# diy_drivermotor.net
KiCad netlist of a schematic drawn in EAGLE
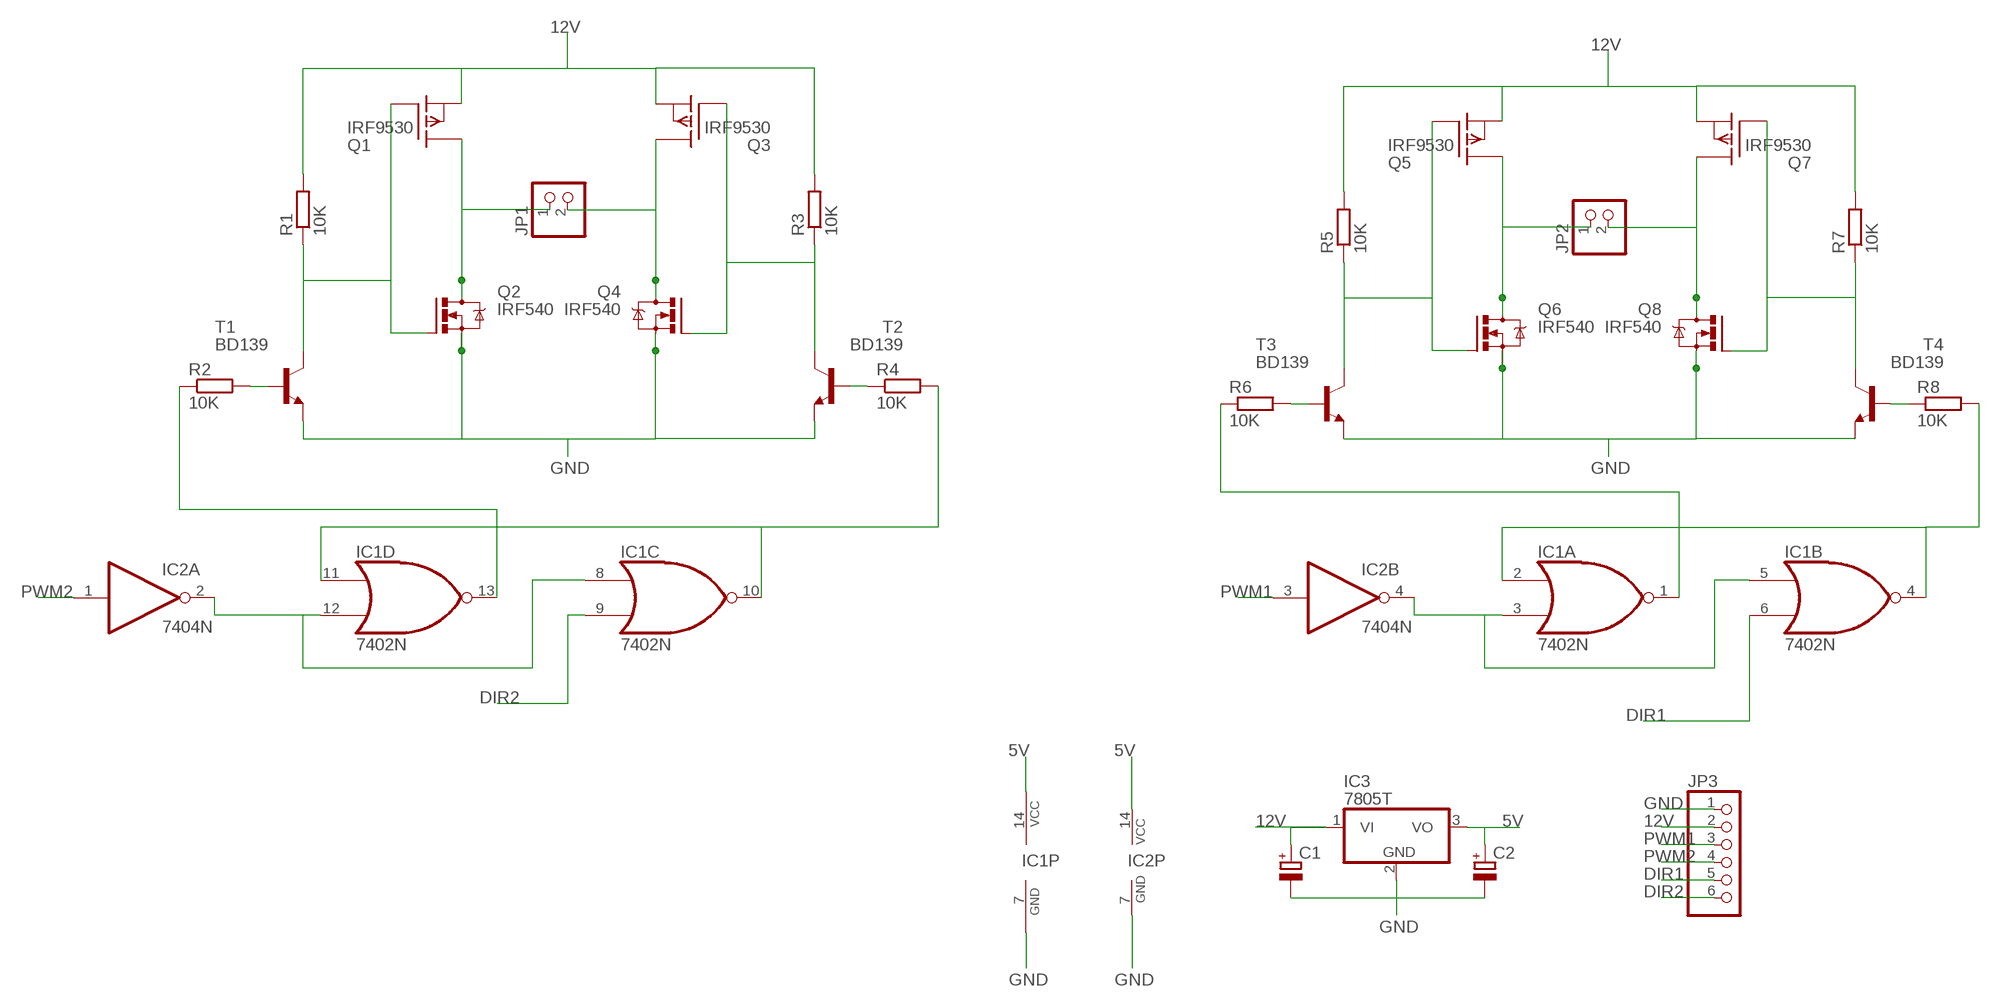
[diagram p0: schematic, sheet 1]

(export (version "E")
  (design (tool "Eeschema 10.0.6"))
  (components
    (comp (ref "C1")
      (value "CPOL-EUE2.5-6")
      (footprint "eagle-import:E2,5-6")
      (libsource (lib "eagle-import") (part "CPOL-EUE2.5-6"))
    )
    (comp (ref "C2")
      (value "CPOL-EUE2.5-6")
      (footprint "eagle-import:E2,5-6")
      (libsource (lib "eagle-import") (part "CPOL-EUE2.5-6"))
    )
    (comp (ref "IC1")
      (value "7402N")
      (footprint "eagle-import:DIL14")
      (libsource (lib "eagle-import") (part "7402N"))
    )
    (comp (ref "IC2")
      (value "7404N")
      (footprint "eagle-import:DIL14")
      (libsource (lib "eagle-import") (part "7404N"))
    )
    (comp (ref "IC3")
      (value "7805T")
      (footprint "eagle-import:TO220H")
      (libsource (lib "eagle-import") (part "78T05"))
    )
    (comp (ref "JP1")
      (value "PINHD-1X2")
      (footprint "eagle-import:1X02")
      (libsource (lib "eagle-import") (part "PINHD-1X2"))
    )
    (comp (ref "JP2")
      (value "PINHD-1X2")
      (footprint "eagle-import:1X02")
      (libsource (lib "eagle-import") (part "PINHD-1X2"))
    )
    (comp (ref "JP3")
      (value "PINHD-1X6")
      (footprint "eagle-import:1X06")
      (libsource (lib "eagle-import") (part "PINHD-1X6"))
    )
    (comp (ref "Q1")
      (value "IRF9530")
      (footprint "eagle-import:TO220")
      (libsource (lib "eagle-import") (part "IRF9530"))
    )
    (comp (ref "Q2")
      (value "IRF540")
      (footprint "eagle-import:TO220BV")
      (libsource (lib "eagle-import") (part "IRF540"))
    )
    (comp (ref "Q3")
      (value "IRF9530")
      (footprint "eagle-import:TO220")
      (libsource (lib "eagle-import") (part "IRF9530"))
    )
    (comp (ref "Q4")
      (value "IRF540")
      (footprint "eagle-import:TO220BV")
      (libsource (lib "eagle-import") (part "IRF540"))
    )
    (comp (ref "Q5")
      (value "IRF9530")
      (footprint "eagle-import:TO220")
      (libsource (lib "eagle-import") (part "IRF9530"))
    )
    (comp (ref "Q6")
      (value "IRF540")
      (footprint "eagle-import:TO220BV")
      (libsource (lib "eagle-import") (part "IRF540"))
    )
    (comp (ref "Q7")
      (value "IRF9530")
      (footprint "eagle-import:TO220")
      (libsource (lib "eagle-import") (part "IRF9530"))
    )
    (comp (ref "Q8")
      (value "IRF540")
      (footprint "eagle-import:TO220BV")
      (libsource (lib "eagle-import") (part "IRF540"))
    )
    (comp (ref "R1")
      (value "10K")
      (footprint "eagle-import:0207_7")
      (libsource (lib "eagle-import") (part "R-EU_0207/7"))
    )
    (comp (ref "R2")
      (value "10K")
      (footprint "eagle-import:0207_7")
      (libsource (lib "eagle-import") (part "R-EU_0207/7"))
    )
    (comp (ref "R3")
      (value "10K")
      (footprint "eagle-import:0207_7")
      (libsource (lib "eagle-import") (part "R-EU_0207/7"))
    )
    (comp (ref "R4")
      (value "10K")
      (footprint "eagle-import:0207_7")
      (libsource (lib "eagle-import") (part "R-EU_0207/7"))
    )
    (comp (ref "R5")
      (value "10K")
      (footprint "eagle-import:0207_7")
      (libsource (lib "eagle-import") (part "R-EU_0207/7"))
    )
    (comp (ref "R6")
      (value "10K")
      (footprint "eagle-import:0207_7")
      (libsource (lib "eagle-import") (part "R-EU_0207/7"))
    )
    (comp (ref "R7")
      (value "10K")
      (footprint "eagle-import:0207_7")
      (libsource (lib "eagle-import") (part "R-EU_0207/7"))
    )
    (comp (ref "R8")
      (value "10K")
      (footprint "eagle-import:0207_7")
      (libsource (lib "eagle-import") (part "R-EU_0207/7"))
    )
    (comp (ref "T1")
      (value "BD139")
      (footprint "eagle-import:TO126")
      (libsource (lib "eagle-import") (part "BD139"))
    )
    (comp (ref "T2")
      (value "BD139")
      (footprint "eagle-import:TO126")
      (libsource (lib "eagle-import") (part "BD139"))
    )
    (comp (ref "T3")
      (value "BD139")
      (footprint "eagle-import:TO126")
      (libsource (lib "eagle-import") (part "BD139"))
    )
    (comp (ref "T4")
      (value "BD139")
      (footprint "eagle-import:TO126")
      (libsource (lib "eagle-import") (part "BD139"))
    )
  )
  (nets
    (net (code "1") (name "/5V") (class "Default")
      (node (ref "C2") (pin "+") (pinfunction "+_+") (pintype "passive"))
      (node (ref "IC1") (pin "14") (pinfunction "VCC_14") (pintype "power_in"))
      (node (ref "IC2") (pin "14") (pinfunction "VCC_14") (pintype "power_in"))
      (node (ref "IC3") (pin "3") (pinfunction "VO_3") (pintype "passive"))
    )
    (net (code "2") (name "/12V") (class "Default")
      (node (ref "C1") (pin "+") (pinfunction "+_+") (pintype "passive"))
      (node (ref "IC3") (pin "1") (pinfunction "VI_1") (pintype "input"))
      (node (ref "JP3") (pin "2") (pinfunction "2_2") (pintype "passive"))
      (node (ref "Q1") (pin "3") (pinfunction "S_3") (pintype "passive"))
      (node (ref "Q3") (pin "3") (pinfunction "S_3") (pintype "passive"))
      (node (ref "Q5") (pin "3") (pinfunction "S_3") (pintype "passive"))
      (node (ref "Q7") (pin "3") (pinfunction "S_3") (pintype "passive"))
      (node (ref "R1") (pin "2") (pinfunction "2_2") (pintype "passive"))
      (node (ref "R3") (pin "2") (pinfunction "2_2") (pintype "passive"))
      (node (ref "R5") (pin "2") (pinfunction "2_2") (pintype "passive"))
      (node (ref "R7") (pin "2") (pinfunction "2_2") (pintype "passive"))
    )
    (net (code "3") (name "/DIR1") (class "Default")
      (node (ref "IC1") (pin "6") (pinfunction "I1_6") (pintype "input"))
      (node (ref "JP3") (pin "5") (pinfunction "5_5") (pintype "passive"))
    )
    (net (code "4") (name "/DIR2") (class "Default")
      (node (ref "IC1") (pin "9") (pinfunction "I1_9") (pintype "input"))
      (node (ref "JP3") (pin "6") (pinfunction "6_6") (pintype "passive"))
    )
    (net (code "5") (name "/GND") (class "Default")
      (node (ref "C1") (pin "-") (pinfunction "-_-") (pintype "passive"))
      (node (ref "C2") (pin "-") (pinfunction "-_-") (pintype "passive"))
      (node (ref "IC1") (pin "7") (pinfunction "GND_7") (pintype "power_in"))
      (node (ref "IC2") (pin "7") (pinfunction "GND_7") (pintype "power_in"))
      (node (ref "IC3") (pin "2") (pinfunction "GND_2") (pintype "passive"))
      (node (ref "JP3") (pin "1") (pinfunction "1_1") (pintype "passive"))
      (node (ref "Q2") (pin "S") (pinfunction "S_S") (pintype "passive"))
      (node (ref "Q4") (pin "S") (pinfunction "S_S") (pintype "passive"))
      (node (ref "Q6") (pin "S") (pinfunction "S_S") (pintype "passive"))
      (node (ref "Q8") (pin "S") (pinfunction "S_S") (pintype "passive"))
      (node (ref "T1") (pin "1") (pinfunction "E_1") (pintype "passive"))
      (node (ref "T2") (pin "1") (pinfunction "E_1") (pintype "passive"))
      (node (ref "T3") (pin "1") (pinfunction "E_1") (pintype "passive"))
      (node (ref "T4") (pin "1") (pinfunction "E_1") (pintype "passive"))
    )
    (net (code "6") (name "/PWM1") (class "Default")
      (node (ref "IC2") (pin "3") (pinfunction "I_3") (pintype "input"))
      (node (ref "JP3") (pin "3") (pinfunction "3_3") (pintype "passive"))
    )
    (net (code "7") (name "/PWM2") (class "Default")
      (node (ref "IC2") (pin "1") (pinfunction "I_1") (pintype "input"))
      (node (ref "JP3") (pin "4") (pinfunction "4_4") (pintype "passive"))
    )
    (net (code "8") (name "Net-(IC1A-I0)") (class "Default")
      (node (ref "IC1") (pin "2") (pinfunction "I0_2") (pintype "input"))
      (node (ref "IC1") (pin "4") (pinfunction "O_4") (pintype "output"))
      (node (ref "R8") (pin "2") (pinfunction "2_2") (pintype "passive"))
    )
    (net (code "9") (name "Net-(IC1A-I1)") (class "Default")
      (node (ref "IC1") (pin "3") (pinfunction "I1_3") (pintype "input"))
      (node (ref "IC1") (pin "5") (pinfunction "I0_5") (pintype "input"))
      (node (ref "IC2") (pin "4") (pinfunction "O_4") (pintype "output"))
    )
    (net (code "10") (name "Net-(IC1A-O)") (class "Default")
      (node (ref "IC1") (pin "1") (pinfunction "O_1") (pintype "output"))
      (node (ref "R6") (pin "1") (pinfunction "1_1") (pintype "passive"))
    )
    (net (code "11") (name "Net-(IC1C-I0)") (class "Default")
      (node (ref "IC1") (pin "12") (pinfunction "I1_12") (pintype "input"))
      (node (ref "IC1") (pin "8") (pinfunction "I0_8") (pintype "input"))
      (node (ref "IC2") (pin "2") (pinfunction "O_2") (pintype "output"))
    )
    (net (code "12") (name "Net-(IC1C-O)") (class "Default")
      (node (ref "IC1") (pin "10") (pinfunction "O_10") (pintype "output"))
      (node (ref "IC1") (pin "11") (pinfunction "I0_11") (pintype "input"))
      (node (ref "R4") (pin "2") (pinfunction "2_2") (pintype "passive"))
    )
    (net (code "13") (name "Net-(IC1D-O)") (class "Default")
      (node (ref "IC1") (pin "13") (pinfunction "O_13") (pintype "output"))
      (node (ref "R2") (pin "1") (pinfunction "1_1") (pintype "passive"))
    )
    (net (code "14") (name "Net-(Q1-D)") (class "Default")
      (node (ref "JP1") (pin "1") (pinfunction "1_1") (pintype "passive"))
      (node (ref "Q1") (pin "2") (pinfunction "D_2") (pintype "passive"))
      (node (ref "Q2") (pin "D") (pinfunction "D_D") (pintype "passive"))
    )
    (net (code "15") (name "Net-(Q1-G)") (class "Default")
      (node (ref "Q1") (pin "1") (pinfunction "G_1") (pintype "passive"))
      (node (ref "Q2") (pin "G") (pinfunction "G_G") (pintype "passive"))
      (node (ref "R1") (pin "1") (pinfunction "1_1") (pintype "passive"))
      (node (ref "T1") (pin "2") (pinfunction "C_2") (pintype "passive"))
    )
    (net (code "16") (name "Net-(Q3-D)") (class "Default")
      (node (ref "JP1") (pin "2") (pinfunction "2_2") (pintype "passive"))
      (node (ref "Q3") (pin "2") (pinfunction "D_2") (pintype "passive"))
      (node (ref "Q4") (pin "D") (pinfunction "D_D") (pintype "passive"))
    )
    (net (code "17") (name "Net-(Q3-G)") (class "Default")
      (node (ref "Q3") (pin "1") (pinfunction "G_1") (pintype "passive"))
      (node (ref "Q4") (pin "G") (pinfunction "G_G") (pintype "passive"))
      (node (ref "R3") (pin "1") (pinfunction "1_1") (pintype "passive"))
      (node (ref "T2") (pin "2") (pinfunction "C_2") (pintype "passive"))
    )
    (net (code "18") (name "Net-(Q5-D)") (class "Default")
      (node (ref "JP2") (pin "1") (pinfunction "1_1") (pintype "passive"))
      (node (ref "Q5") (pin "2") (pinfunction "D_2") (pintype "passive"))
      (node (ref "Q6") (pin "D") (pinfunction "D_D") (pintype "passive"))
    )
    (net (code "19") (name "Net-(Q5-G)") (class "Default")
      (node (ref "Q5") (pin "1") (pinfunction "G_1") (pintype "passive"))
      (node (ref "Q6") (pin "G") (pinfunction "G_G") (pintype "passive"))
      (node (ref "R5") (pin "1") (pinfunction "1_1") (pintype "passive"))
      (node (ref "T3") (pin "2") (pinfunction "C_2") (pintype "passive"))
    )
    (net (code "20") (name "Net-(Q7-D)") (class "Default")
      (node (ref "JP2") (pin "2") (pinfunction "2_2") (pintype "passive"))
      (node (ref "Q7") (pin "2") (pinfunction "D_2") (pintype "passive"))
      (node (ref "Q8") (pin "D") (pinfunction "D_D") (pintype "passive"))
    )
    (net (code "21") (name "Net-(Q7-G)") (class "Default")
      (node (ref "Q7") (pin "1") (pinfunction "G_1") (pintype "passive"))
      (node (ref "Q8") (pin "G") (pinfunction "G_G") (pintype "passive"))
      (node (ref "R7") (pin "1") (pinfunction "1_1") (pintype "passive"))
      (node (ref "T4") (pin "2") (pinfunction "C_2") (pintype "passive"))
    )
    (net (code "22") (name "Net-(T1-B)") (class "Default")
      (node (ref "R2") (pin "2") (pinfunction "2_2") (pintype "passive"))
      (node (ref "T1") (pin "3") (pinfunction "B_3") (pintype "passive"))
    )
    (net (code "23") (name "Net-(T2-B)") (class "Default")
      (node (ref "R4") (pin "1") (pinfunction "1_1") (pintype "passive"))
      (node (ref "T2") (pin "3") (pinfunction "B_3") (pintype "passive"))
    )
    (net (code "24") (name "Net-(T3-B)") (class "Default")
      (node (ref "R6") (pin "2") (pinfunction "2_2") (pintype "passive"))
      (node (ref "T3") (pin "3") (pinfunction "B_3") (pintype "passive"))
    )
    (net (code "25") (name "Net-(T4-B)") (class "Default")
      (node (ref "R8") (pin "1") (pinfunction "1_1") (pintype "passive"))
      (node (ref "T4") (pin "3") (pinfunction "B_3") (pintype "passive"))
    )
  )
)
